# XRACER-SERIALS-R07.net
KiCad netlist of a schematic drawn in Altium Designer
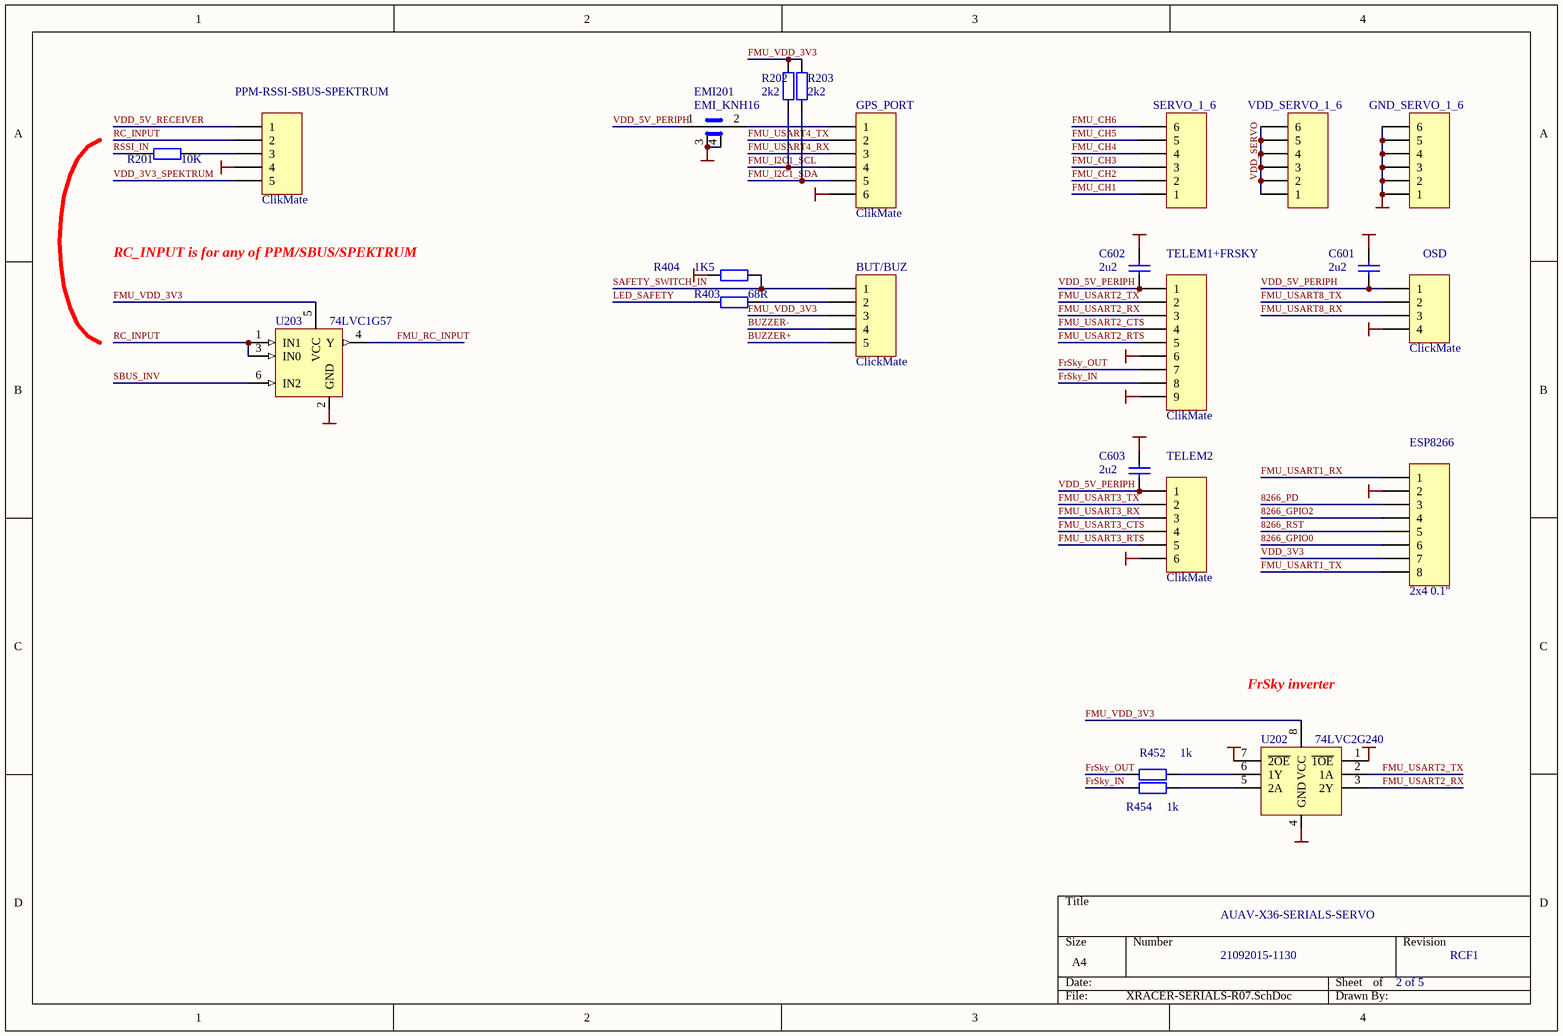
[diagram p0: XRACER-SERIALS-R07.SchDoc]

(export (version "E")
  (design (tool "Eeschema 10.0.6"))
  (components
    (comp (ref "BUT/BUZ")
      (value "ClickMate")
      (footprint "Molex_Clik_1.25_5H")
      (description "Header, 5-Pin")
      (fields (field (name "PUBLISHER") "Altium Limited"))
      (libsource (lib "Miscellaneous Connectors") (part "Header 5"))
    )
    (comp (ref "C601")
      (value "2u2")
      (footprint "0402A")
      (description "Capacitor")
      (fields (field (name "PUBLISHER") "Altium Limited"))
      (libsource (lib "Miscellaneous Devices") (part "Cap"))
    )
    (comp (ref "C602")
      (value "2u2")
      (footprint "0402A")
      (description "Capacitor")
      (fields (field (name "PUBLISHER") "Altium Limited"))
      (libsource (lib "Miscellaneous Devices") (part "Cap"))
    )
    (comp (ref "C603")
      (value "2u2")
      (footprint "0402A")
      (description "Capacitor")
      (fields (field (name "PUBLISHER") "Altium Limited"))
      (libsource (lib "Miscellaneous Devices") (part "Cap"))
    )
    (comp (ref "EMI201")
      (value "EMI_KNH16")
      (footprint "EMI_KNH16_0603")
      (libsource (lib "My_Altium") (part "EMI_KNH16"))
    )
    (comp (ref "ESP8266")
      (value "2x4 0.1\"")
      (footprint "2.54mm_2x4_SMD_female")
      (description "Header, 8-Pin")
      (fields (field (name "PUBLISHER") "Altium Limited"))
      (libsource (lib "Miscellaneous Connectors") (part "Header 8"))
    )
    (comp (ref "GND_SERVO_1_6")
      (value "Header 6")
      (footprint "HDR1X6")
      (description "Header, 6-Pin")
      (fields (field (name "PUBLISHER") "Altium Limited"))
      (libsource (lib "Miscellaneous Connectors") (part "Header 6"))
    )
    (comp (ref "GPS_PORT")
      (value "ClikMate")
      (footprint "Molex_Clok_1.25_6H")
      (description "Header, 6-Pin")
      (fields (field (name "PUBLISHER") "Altium Limited"))
      (libsource (lib "") (part "Header 6_1"))
    )
    (comp (ref "OSD")
      (value "ClickMate")
      (footprint "Molex_1.25_click_4")
      (description "Header, 4-Pin")
      (fields (field (name "PUBLISHER") "Altium Limited"))
      (libsource (lib "Miscellaneous Connectors") (part "Header 4"))
    )
    (comp (ref "PPM-RSSI-SBUS-SPEKTRUM")
      (value "ClikMate")
      (footprint "Molex_Clik_1.25_5H")
      (description "Header, 5-Pin")
      (fields (field (name "PUBLISHER") "Altium Limited"))
      (libsource (lib "Miscellaneous Connectors") (part "Header 5"))
    )
    (comp (ref "R201")
      (value "10K")
      (footprint "0402A")
      (description "Resistor")
      (fields (field (name "PUBLISHER") "Altium Limited"))
      (libsource (lib "Miscellaneous Devices") (part "Res2"))
    )
    (comp (ref "R202")
      (value "2k2")
      (footprint "0402A")
      (description "Resistor")
      (fields (field (name "PUBLISHER") "Altium Limited"))
      (libsource (lib "") (part "Res2_1"))
    )
    (comp (ref "R203")
      (value "2k2")
      (footprint "0402A")
      (description "Resistor")
      (fields (field (name "PUBLISHER") "Altium Limited"))
      (libsource (lib "") (part "Res2_1"))
    )
    (comp (ref "R403")
      (value "68R")
      (footprint "0402A")
      (description "Resistor")
      (fields (field (name "PUBLISHER") "Altium Limited"))
      (libsource (lib "Miscellaneous Devices") (part "Res2"))
    )
    (comp (ref "R404")
      (value "1K5")
      (footprint "0402A")
      (description "Resistor")
      (fields (field (name "PUBLISHER") "Altium Limited"))
      (libsource (lib "Miscellaneous Devices") (part "Res2"))
    )
    (comp (ref "R452")
      (value "1k")
      (footprint "0402A")
      (description "Resistor")
      (fields (field (name "PUBLISHER") "Altium Limited"))
      (libsource (lib "") (part "Res2_2"))
    )
    (comp (ref "R454")
      (value "1k")
      (footprint "0402A")
      (description "Resistor")
      (fields (field (name "PUBLISHER") "Altium Limited"))
      (libsource (lib "") (part "Res2_2"))
    )
    (comp (ref "SERVO_1_6")
      (value "Header 6")
      (footprint "HDR1X6")
      (description "Header, 6-Pin")
      (fields (field (name "PUBLISHER") "Altium Limited"))
      (libsource (lib "Miscellaneous Connectors") (part "Header 6"))
    )
    (comp (ref "TELEM1+FRSKY")
      (value "ClikMate")
      (footprint "Molex_Click_1.25_9H")
      (description "Header, 9-Pin")
      (fields (field (name "PUBLISHER") "Altium Limited"))
      (libsource (lib "Miscellaneous Connectors") (part "Header 9"))
    )
    (comp (ref "TELEM2")
      (value "ClikMate")
      (footprint "Molex_Clok_1.25_6H")
      (description "Header, 6-Pin")
      (fields (field (name "PUBLISHER") "Altium Limited"))
      (libsource (lib "") (part "Header 6_1"))
    )
    (comp (ref "U202")
      (value "74LVC2G240")
      (footprint "ssop-8")
      (libsource (lib "My_Altium") (part "74LVC2G240"))
    )
    (comp (ref "U203")
      (value "74LVC1G57")
      (footprint "sot323-6")
      (libsource (lib "My_Altium") (part "74LVC1G57"))
    )
    (comp (ref "VDD_SERVO_1_6")
      (value "Header 6")
      (footprint "HDR1X6")
      (description "Header, 6-Pin")
      (fields (field (name "PUBLISHER") "Altium Limited"))
      (libsource (lib "Miscellaneous Connectors") (part "Header 6"))
    )
  )
  (nets
    (net (code "1") (name "/8266_GPIO0") (class "Default")
      (node (ref "ESP8266") (pin "6") (pinfunction "6_6") (pintype "passive"))
    )
    (net (code "2") (name "/8266_GPIO2") (class "Default")
      (node (ref "ESP8266") (pin "4") (pinfunction "4_4") (pintype "passive"))
    )
    (net (code "3") (name "/8266_PD") (class "Default")
      (node (ref "ESP8266") (pin "3") (pinfunction "3_3") (pintype "passive"))
    )
    (net (code "4") (name "/8266_RST") (class "Default")
      (node (ref "ESP8266") (pin "5") (pinfunction "5_5") (pintype "passive"))
    )
    (net (code "5") (name "/BUZZER+") (class "Default")
      (node (ref "BUT/BUZ") (pin "5") (pinfunction "5_5") (pintype "passive"))
    )
    (net (code "6") (name "/BUZZER-") (class "Default")
      (node (ref "BUT/BUZ") (pin "4") (pinfunction "4_4") (pintype "passive"))
    )
    (net (code "7") (name "/FMU_CH1") (class "Default")
      (node (ref "SERVO_1_6") (pin "1") (pinfunction "1_1") (pintype "passive"))
    )
    (net (code "8") (name "/FMU_CH2") (class "Default")
      (node (ref "SERVO_1_6") (pin "2") (pinfunction "2_2") (pintype "passive"))
    )
    (net (code "9") (name "/FMU_CH3") (class "Default")
      (node (ref "SERVO_1_6") (pin "3") (pinfunction "3_3") (pintype "passive"))
    )
    (net (code "10") (name "/FMU_CH4") (class "Default")
      (node (ref "SERVO_1_6") (pin "4") (pinfunction "4_4") (pintype "passive"))
    )
    (net (code "11") (name "/FMU_CH5") (class "Default")
      (node (ref "SERVO_1_6") (pin "5") (pinfunction "5_5") (pintype "passive"))
    )
    (net (code "12") (name "/FMU_CH6") (class "Default")
      (node (ref "SERVO_1_6") (pin "6") (pinfunction "6_6") (pintype "passive"))
    )
    (net (code "13") (name "/FMU_I2C1_SCL") (class "Default")
      (node (ref "GPS_PORT") (pin "4") (pinfunction "4_4") (pintype "passive"))
      (node (ref "R202") (pin "2") (pinfunction "2_2") (pintype "passive"))
    )
    (net (code "14") (name "/FMU_I2C1_SDA") (class "Default")
      (node (ref "GPS_PORT") (pin "5") (pinfunction "5_5") (pintype "passive"))
      (node (ref "R203") (pin "2") (pinfunction "2_2") (pintype "passive"))
    )
    (net (code "15") (name "/FMU_RC_INPUT") (class "Default")
      (node (ref "U203") (pin "4") (pinfunction "Y_4") (pintype "output"))
    )
    (net (code "16") (name "/FMU_USART1_RX") (class "Default")
      (node (ref "ESP8266") (pin "1") (pinfunction "1_1") (pintype "passive"))
    )
    (net (code "17") (name "/FMU_USART1_TX") (class "Default")
      (node (ref "ESP8266") (pin "8") (pinfunction "8_8") (pintype "passive"))
    )
    (net (code "18") (name "/FMU_USART2_CTS") (class "Default")
      (node (ref "TELEM1+FRSKY") (pin "4") (pinfunction "4_4") (pintype "passive"))
    )
    (net (code "19") (name "/FMU_USART2_RTS") (class "Default")
      (node (ref "TELEM1+FRSKY") (pin "5") (pinfunction "5_5") (pintype "passive"))
    )
    (net (code "20") (name "/FMU_USART2_RX") (class "Default")
      (node (ref "TELEM1+FRSKY") (pin "3") (pinfunction "3_3") (pintype "passive"))
      (node (ref "U202") (pin "3") (pinfunction "2Y_3") (pintype "passive"))
    )
    (net (code "21") (name "/FMU_USART2_TX") (class "Default")
      (node (ref "TELEM1+FRSKY") (pin "2") (pinfunction "2_2") (pintype "passive"))
      (node (ref "U202") (pin "2") (pinfunction "1A_2") (pintype "passive"))
    )
    (net (code "22") (name "/FMU_USART3_CTS") (class "Default")
      (node (ref "TELEM2") (pin "4") (pinfunction "4_4") (pintype "passive"))
    )
    (net (code "23") (name "/FMU_USART3_RTS") (class "Default")
      (node (ref "TELEM2") (pin "5") (pinfunction "5_5") (pintype "passive"))
    )
    (net (code "24") (name "/FMU_USART3_RX") (class "Default")
      (node (ref "TELEM2") (pin "3") (pinfunction "3_3") (pintype "passive"))
    )
    (net (code "25") (name "/FMU_USART3_TX") (class "Default")
      (node (ref "TELEM2") (pin "2") (pinfunction "2_2") (pintype "passive"))
    )
    (net (code "26") (name "/FMU_USART4_RX") (class "Default")
      (node (ref "GPS_PORT") (pin "3") (pinfunction "3_3") (pintype "passive"))
    )
    (net (code "27") (name "/FMU_USART4_TX") (class "Default")
      (node (ref "GPS_PORT") (pin "2") (pinfunction "2_2") (pintype "passive"))
    )
    (net (code "28") (name "/FMU_USART8_RX") (class "Default")
      (node (ref "OSD") (pin "3") (pinfunction "3_3") (pintype "passive"))
    )
    (net (code "29") (name "/FMU_USART8_TX") (class "Default")
      (node (ref "OSD") (pin "2") (pinfunction "2_2") (pintype "passive"))
    )
    (net (code "30") (name "/FMU_VDD_3V3") (class "Default")
      (node (ref "BUT/BUZ") (pin "3") (pinfunction "3_3") (pintype "passive"))
      (node (ref "R202") (pin "1") (pinfunction "1_1") (pintype "passive"))
      (node (ref "R203") (pin "1") (pinfunction "1_1") (pintype "passive"))
      (node (ref "U202") (pin "8") (pinfunction "VCC_8") (pintype "passive"))
      (node (ref "U203") (pin "5") (pinfunction "VCC_5") (pintype "power_in"))
    )
    (net (code "31") (name "/FrSky_IN") (class "Default")
      (node (ref "R454") (pin "1") (pinfunction "1_1") (pintype "passive"))
      (node (ref "TELEM1+FRSKY") (pin "8") (pinfunction "8_8") (pintype "passive"))
    )
    (net (code "32") (name "/FrSky_OUT") (class "Default")
      (node (ref "R452") (pin "1") (pinfunction "1_1") (pintype "passive"))
      (node (ref "TELEM1+FRSKY") (pin "7") (pinfunction "7_7") (pintype "passive"))
    )
    (net (code "33") (name "/LED_SAFETY") (class "Default")
      (node (ref "R403") (pin "2") (pinfunction "2_2") (pintype "passive"))
    )
    (net (code "34") (name "/RC_INPUT") (class "Default")
      (node (ref "PPM-RSSI-SBUS-SPEKTRUM") (pin "2") (pinfunction "2_2") (pintype "passive"))
      (node (ref "U203") (pin "1") (pinfunction "IN1_1") (pintype "input"))
      (node (ref "U203") (pin "3") (pinfunction "IN0_3") (pintype "input"))
    )
    (net (code "35") (name "/RSSI_IN") (class "Default")
      (node (ref "R201") (pin "2") (pinfunction "2_2") (pintype "passive"))
    )
    (net (code "36") (name "/SAFETY_SWITCH_IN") (class "Default")
      (node (ref "BUT/BUZ") (pin "1") (pinfunction "1_1") (pintype "passive"))
      (node (ref "R404") (pin "1") (pinfunction "1_1") (pintype "passive"))
    )
    (net (code "37") (name "/SBUS_INV") (class "Default")
      (node (ref "U203") (pin "6") (pinfunction "IN2_6") (pintype "input"))
    )
    (net (code "38") (name "/VDD_3V3") (class "Default")
      (node (ref "ESP8266") (pin "7") (pinfunction "7_7") (pintype "passive"))
    )
    (net (code "39") (name "/VDD_3V3_SPEKTRUM") (class "Default")
      (node (ref "PPM-RSSI-SBUS-SPEKTRUM") (pin "5") (pinfunction "5_5") (pintype "passive"))
    )
    (net (code "40") (name "/VDD_5V_PERIPH") (class "Default")
      (node (ref "C601") (pin "1") (pinfunction "1_1") (pintype "passive"))
      (node (ref "C602") (pin "1") (pinfunction "1_1") (pintype "passive"))
      (node (ref "C603") (pin "1") (pinfunction "1_1") (pintype "passive"))
      (node (ref "EMI201") (pin "1") (pinfunction "L1_1") (pintype "passive"))
      (node (ref "OSD") (pin "1") (pinfunction "1_1") (pintype "passive"))
      (node (ref "TELEM1+FRSKY") (pin "1") (pinfunction "1_1") (pintype "passive"))
      (node (ref "TELEM2") (pin "1") (pinfunction "1_1") (pintype "passive"))
    )
    (net (code "41") (name "/VDD_5V_RECEIVER") (class "Default")
      (node (ref "PPM-RSSI-SBUS-SPEKTRUM") (pin "1") (pinfunction "1_1") (pintype "passive"))
    )
    (net (code "42") (name "/VDD_SERVO") (class "Default")
      (node (ref "VDD_SERVO_1_6") (pin "1") (pinfunction "1_1") (pintype "passive"))
      (node (ref "VDD_SERVO_1_6") (pin "2") (pinfunction "2_2") (pintype "passive"))
      (node (ref "VDD_SERVO_1_6") (pin "3") (pinfunction "3_3") (pintype "passive"))
      (node (ref "VDD_SERVO_1_6") (pin "4") (pinfunction "4_4") (pintype "passive"))
      (node (ref "VDD_SERVO_1_6") (pin "5") (pinfunction "5_5") (pintype "passive"))
      (node (ref "VDD_SERVO_1_6") (pin "6") (pinfunction "6_6") (pintype "passive"))
    )
    (net (code "43") (name "GND") (class "Default")
      (node (ref "C601") (pin "2") (pinfunction "2_2") (pintype "passive"))
      (node (ref "C602") (pin "2") (pinfunction "2_2") (pintype "passive"))
      (node (ref "C603") (pin "2") (pinfunction "2_2") (pintype "passive"))
      (node (ref "EMI201") (pin "3") (pinfunction "G_3") (pintype "power_in"))
      (node (ref "EMI201") (pin "4") (pinfunction "G_4") (pintype "passive"))
      (node (ref "ESP8266") (pin "2") (pinfunction "2_2") (pintype "passive"))
      (node (ref "GND_SERVO_1_6") (pin "1") (pinfunction "1_1") (pintype "passive"))
      (node (ref "GND_SERVO_1_6") (pin "2") (pinfunction "2_2") (pintype "passive"))
      (node (ref "GND_SERVO_1_6") (pin "3") (pinfunction "3_3") (pintype "passive"))
      (node (ref "GND_SERVO_1_6") (pin "4") (pinfunction "4_4") (pintype "passive"))
      (node (ref "GND_SERVO_1_6") (pin "5") (pinfunction "5_5") (pintype "passive"))
      (node (ref "GND_SERVO_1_6") (pin "6") (pinfunction "6_6") (pintype "passive"))
      (node (ref "GPS_PORT") (pin "6") (pinfunction "6_6") (pintype "passive"))
      (node (ref "OSD") (pin "4") (pinfunction "4_4") (pintype "passive"))
      (node (ref "PPM-RSSI-SBUS-SPEKTRUM") (pin "4") (pinfunction "4_4") (pintype "passive"))
      (node (ref "R404") (pin "2") (pinfunction "2_2") (pintype "passive"))
      (node (ref "TELEM1+FRSKY") (pin "6") (pinfunction "6_6") (pintype "passive"))
      (node (ref "TELEM1+FRSKY") (pin "9") (pinfunction "9_9") (pintype "passive"))
      (node (ref "TELEM2") (pin "6") (pinfunction "6_6") (pintype "passive"))
      (node (ref "U202") (pin "1") (pinfunction "~{1OE}_1") (pintype "passive"))
      (node (ref "U202") (pin "4") (pinfunction "GND_4") (pintype "passive"))
      (node (ref "U202") (pin "7") (pinfunction "~{2OE}_7") (pintype "passive"))
      (node (ref "U203") (pin "2") (pinfunction "GND_2") (pintype "power_in"))
    )
    (net (code "44") (name "Net-(BUT/BUZ-Pad2)") (class "Default")
      (node (ref "BUT/BUZ") (pin "2") (pinfunction "2_2") (pintype "passive"))
      (node (ref "R403") (pin "1") (pinfunction "1_1") (pintype "passive"))
    )
    (net (code "45") (name "Net-(EMI201-L2)") (class "Default")
      (node (ref "EMI201") (pin "2") (pinfunction "L2_2") (pintype "passive"))
      (node (ref "GPS_PORT") (pin "1") (pinfunction "1_1") (pintype "passive"))
    )
    (net (code "46") (name "Net-(PPM-RSSI-SBUS-SPEKTRUM-Pad3)") (class "Default")
      (node (ref "PPM-RSSI-SBUS-SPEKTRUM") (pin "3") (pinfunction "3_3") (pintype "passive"))
      (node (ref "R201") (pin "1") (pinfunction "1_1") (pintype "passive"))
    )
    (net (code "47") (name "Net-(U202-1Y)") (class "Default")
      (node (ref "R452") (pin "2") (pinfunction "2_2") (pintype "passive"))
      (node (ref "U202") (pin "6") (pinfunction "1Y_6") (pintype "passive"))
    )
    (net (code "48") (name "Net-(U202-2A)") (class "Default")
      (node (ref "R454") (pin "2") (pinfunction "2_2") (pintype "passive"))
      (node (ref "U202") (pin "5") (pinfunction "2A_5") (pintype "passive"))
    )
  )
)
